# pic.net
KiCad netlist of a schematic drawn in Altium Designer
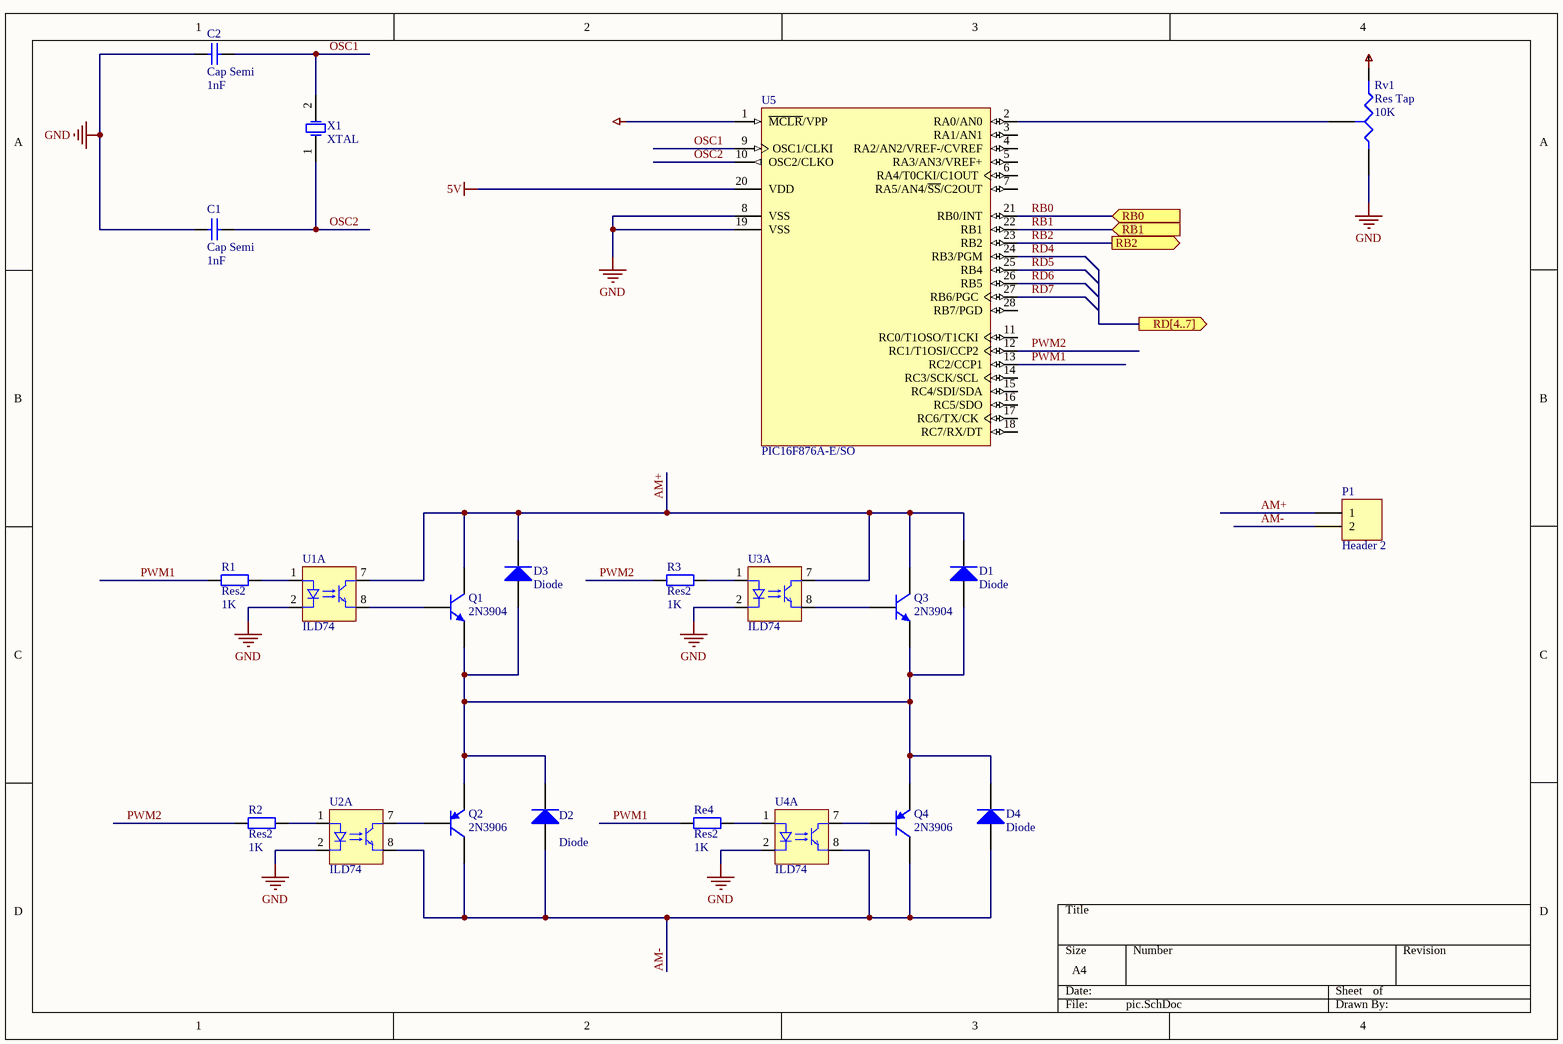
[diagram p0: pic.SchDoc]

(export (version "E")
  (design (tool "Eeschema 10.0.6"))
  (components
    (comp (ref "C1")
      (value "Cap Semi")
      (footprint "C1206")
      (description "Capacitor (Semiconductor SIM Model)")
      (fields (field (name "ALTIUM_VALUE") "1nF") (field (name "PUBLISHER") "Altium Limited"))
      (libsource (lib "Miscellaneous Devices") (part "Cap Semi"))
    )
    (comp (ref "C2")
      (value "Cap Semi")
      (footprint "C1206")
      (description "Capacitor (Semiconductor SIM Model)")
      (fields (field (name "ALTIUM_VALUE") "1nF") (field (name "PUBLISHER") "Altium Limited"))
      (libsource (lib "Miscellaneous Devices") (part "Cap Semi"))
    )
    (comp (ref "D1")
      (value "Diode")
      (footprint "SMC")
      (description "Default Diode")
      (fields (field (name "PUBLISHER") "Altium Limited"))
      (libsource (lib "Miscellaneous Devices") (part "Diode"))
    )
    (comp (ref "D2")
      (value "Diode")
      (footprint "SMC")
      (description "Default Diode")
      (fields (field (name "PUBLISHER") "Altium Limited"))
      (libsource (lib "Miscellaneous Devices") (part "Diode"))
    )
    (comp (ref "D3")
      (value "Diode")
      (footprint "SMC")
      (description "Default Diode")
      (fields (field (name "PUBLISHER") "Altium Limited"))
      (libsource (lib "Miscellaneous Devices") (part "Diode"))
    )
    (comp (ref "D4")
      (value "Diode")
      (footprint "SMC")
      (description "Default Diode")
      (fields (field (name "PUBLISHER") "Altium Limited"))
      (libsource (lib "Miscellaneous Devices") (part "Diode"))
    )
    (comp (ref "P1")
      (value "Header 2")
      (footprint "HDR1X2")
      (description "Header, 2-Pin")
      (fields (field (name "PUBLISHER") "Altium Limited"))
      (libsource (lib "Miscellaneous Connectors") (part "Header 2"))
    )
    (comp (ref "Q1")
      (value "2N3904")
      (footprint "TO-92A")
      (description "NPN General Purpose Amplifier")
      (fields (field (name "PUBLISHER") "Altium Limited"))
      (libsource (lib "Miscellaneous Devices") (part "2N3904"))
    )
    (comp (ref "Q2")
      (value "2N3906")
      (footprint "TO-92A")
      (description "PNP General Purpose Amplifier")
      (fields (field (name "PUBLISHER") "Altium Limited"))
      (libsource (lib "Miscellaneous Devices") (part "2N3906"))
    )
    (comp (ref "Q3")
      (value "2N3904")
      (footprint "TO-92A")
      (description "NPN General Purpose Amplifier")
      (fields (field (name "PUBLISHER") "Altium Limited"))
      (libsource (lib "Miscellaneous Devices") (part "2N3904"))
    )
    (comp (ref "Q4")
      (value "2N3906")
      (footprint "TO-92A")
      (description "PNP General Purpose Amplifier")
      (fields (field (name "PUBLISHER") "Altium Limited"))
      (libsource (lib "Miscellaneous Devices") (part "2N3906"))
    )
    (comp (ref "R1")
      (value "Res2")
      (footprint "AXIAL-0.4")
      (description "Resistor")
      (fields (field (name "ALTIUM_VALUE") "1K") (field (name "PUBLISHER") "Altium Limited"))
      (libsource (lib "Miscellaneous Devices") (part "Res2"))
    )
    (comp (ref "R2")
      (value "Res2")
      (footprint "AXIAL-0.4")
      (description "Resistor")
      (fields (field (name "ALTIUM_VALUE") "1K") (field (name "PUBLISHER") "Altium Limited"))
      (libsource (lib "Miscellaneous Devices") (part "Res2"))
    )
    (comp (ref "R3")
      (value "Res2")
      (footprint "AXIAL-0.4")
      (description "Resistor")
      (fields (field (name "ALTIUM_VALUE") "1K") (field (name "PUBLISHER") "Altium Limited"))
      (libsource (lib "Miscellaneous Devices") (part "Res2"))
    )
    (comp (ref "Re4")
      (value "Res2")
      (footprint "AXIAL-0.4")
      (description "Resistor")
      (fields (field (name "ALTIUM_VALUE") "1K") (field (name "PUBLISHER") "Altium Limited"))
      (libsource (lib "Miscellaneous Devices") (part "Res2"))
    )
    (comp (ref "Rv1")
      (value "Res Tap")
      (footprint "VR3")
      (description "Tapped Resistor")
      (fields (field (name "ALTIUM_VALUE") "10K") (field (name "PUBLISHER") "Altium Limited"))
      (libsource (lib "Miscellaneous Devices") (part "Res Tap"))
    )
    (comp (ref "U1")
      (value "ILD74")
      (footprint "DIP8")
      (description "Optocoupler, Phototransistor Output, Dual Channel, TTL Compatible, Pb-free")
      (fields (field (name "PUBLISHER") "Altium Limited"))
      (libsource (lib "Vishay Optoelectronic Optocoupler") (part "ILD74"))
    )
    (comp (ref "U2")
      (value "ILD74")
      (footprint "DIP8")
      (description "Optocoupler, Phototransistor Output, Dual Channel, TTL Compatible, Pb-free")
      (fields (field (name "PUBLISHER") "Altium Limited"))
      (libsource (lib "Vishay Optoelectronic Optocoupler") (part "ILD74"))
    )
    (comp (ref "U3")
      (value "ILD74")
      (footprint "DIP8")
      (description "Optocoupler, Phototransistor Output, Dual Channel, TTL Compatible, Pb-free")
      (fields (field (name "PUBLISHER") "Altium Limited"))
      (libsource (lib "Vishay Optoelectronic Optocoupler") (part "ILD74"))
    )
    (comp (ref "U4")
      (value "ILD74")
      (footprint "DIP8")
      (description "Optocoupler, Phototransistor Output, Dual Channel, TTL Compatible, Pb-free")
      (fields (field (name "PUBLISHER") "Altium Limited"))
      (libsource (lib "Vishay Optoelectronic Optocoupler") (part "ILD74"))
    )
    (comp (ref "U5")
      (value "PIC16F876A-E/SO")
      (footprint "SOIC-SO28_N")
      (fields (field (name "PUBLISHER") "Altium Limited"))
      (libsource (lib "Microchip Microcontroller 8-Bit PIC16") (part "PIC16F876A-E/SO"))
    )
    (comp (ref "X1")
      (value "XTAL")
      (footprint "R38")
      (description "Crystal Oscillator")
      (fields (field (name "PUBLISHER") "Altium Limited"))
      (libsource (lib "Miscellaneous Devices") (part "XTAL"))
    )
  )
  (nets
    (net (code "1") (name "/AM+") (class "Default")
      (node (ref "D1") (pin "2") (pinfunction "K_2") (pintype "passive"))
      (node (ref "D3") (pin "2") (pinfunction "K_2") (pintype "passive"))
      (node (ref "P1") (pin "1") (pinfunction "1_1") (pintype "passive"))
      (node (ref "Q1") (pin "3") (pinfunction "C_3") (pintype "passive"))
      (node (ref "Q3") (pin "3") (pinfunction "C_3") (pintype "passive"))
      (node (ref "U1") (pin "7") (pinfunction "C_7") (pintype "passive"))
      (node (ref "U3") (pin "7") (pinfunction "C_7") (pintype "passive"))
    )
    (net (code "2") (name "/AM-") (class "Default")
      (node (ref "D2") (pin "1") (pinfunction "A_1") (pintype "passive"))
      (node (ref "D4") (pin "1") (pinfunction "A_1") (pintype "passive"))
      (node (ref "P1") (pin "2") (pinfunction "2_2") (pintype "passive"))
      (node (ref "Q2") (pin "3") (pinfunction "C_3") (pintype "passive"))
      (node (ref "Q4") (pin "3") (pinfunction "C_3") (pintype "passive"))
      (node (ref "U2") (pin "8") (pinfunction "E_8") (pintype "passive"))
      (node (ref "U4") (pin "8") (pinfunction "E_8") (pintype "passive"))
    )
    (net (code "3") (name "/OSC1") (class "Default")
      (node (ref "C2") (pin "2") (pinfunction "2_2") (pintype "passive"))
      (node (ref "U5") (pin "9") (pinfunction "OSC1/CLKI_9") (pintype "input"))
      (node (ref "X1") (pin "2") (pinfunction "OSC2_2") (pintype "passive"))
    )
    (net (code "4") (name "/OSC2") (class "Default")
      (node (ref "C1") (pin "2") (pinfunction "2_2") (pintype "passive"))
      (node (ref "U5") (pin "10") (pinfunction "OSC2/CLKO_10") (pintype "output"))
      (node (ref "X1") (pin "1") (pinfunction "OSC1_1") (pintype "passive"))
    )
    (net (code "5") (name "/PWM1") (class "Default")
      (node (ref "R1") (pin "1") (pinfunction "1_1") (pintype "passive"))
      (node (ref "Re4") (pin "1") (pinfunction "1_1") (pintype "passive"))
      (node (ref "U5") (pin "13") (pinfunction "RC2/CCP1_13") (pintype "bidirectional"))
    )
    (net (code "6") (name "/PWM2") (class "Default")
      (node (ref "R2") (pin "1") (pinfunction "1_1") (pintype "passive"))
      (node (ref "R3") (pin "1") (pinfunction "1_1") (pintype "passive"))
      (node (ref "U5") (pin "12") (pinfunction "RC1/T1OSI/CCP2_12") (pintype "bidirectional"))
    )
    (net (code "7") (name "/RB0") (class "Default")
      (node (ref "U5") (pin "21") (pinfunction "RB0/INT_21") (pintype "bidirectional"))
    )
    (net (code "8") (name "/RB1") (class "Default")
      (node (ref "U5") (pin "22") (pinfunction "RB1_22") (pintype "bidirectional"))
    )
    (net (code "9") (name "/RB2") (class "Default")
      (node (ref "U5") (pin "23") (pinfunction "RB2_23") (pintype "bidirectional"))
    )
    (net (code "10") (name "/RD4") (class "Default")
      (node (ref "U5") (pin "24") (pinfunction "RB3/PGM_24") (pintype "bidirectional"))
    )
    (net (code "11") (name "/RD5") (class "Default")
      (node (ref "U5") (pin "25") (pinfunction "RB4_25") (pintype "bidirectional"))
    )
    (net (code "12") (name "/RD6") (class "Default")
      (node (ref "U5") (pin "26") (pinfunction "RB5_26") (pintype "bidirectional"))
    )
    (net (code "13") (name "/RD7") (class "Default")
      (node (ref "U5") (pin "27") (pinfunction "RB6/PGC_27") (pintype "bidirectional"))
    )
    (net (code "15") (name "5V") (class "Default")
      (node (ref "U5") (pin "20") (pinfunction "VDD_20") (pintype "power_in"))
    )
    (net (code "16") (name "<NO NET>") (class "Default")
      (node (ref "U5") (pin "1") (pinfunction "~{MCLR}/VPP_1") (pintype "input"))
    )
    (net (code "17") (name "GND") (class "Default")
      (node (ref "C1") (pin "1") (pinfunction "1_1") (pintype "passive"))
      (node (ref "C2") (pin "1") (pinfunction "1_1") (pintype "passive"))
      (node (ref "Rv1") (pin "1") (pinfunction "A_1") (pintype "passive"))
      (node (ref "U1") (pin "2") (pinfunction "K_2") (pintype "passive"))
      (node (ref "U2") (pin "2") (pinfunction "K_2") (pintype "passive"))
      (node (ref "U3") (pin "2") (pinfunction "K_2") (pintype "passive"))
      (node (ref "U4") (pin "2") (pinfunction "K_2") (pintype "passive"))
      (node (ref "U5") (pin "19") (pinfunction "VSS_19") (pintype "power_in"))
      (node (ref "U5") (pin "8") (pinfunction "VSS_8") (pintype "power_in"))
    )
    (net (code "18") (name "Net-(D1-A)") (class "Default")
      (node (ref "D1") (pin "1") (pinfunction "A_1") (pintype "passive"))
      (node (ref "D2") (pin "2") (pinfunction "K_2") (pintype "passive"))
      (node (ref "D3") (pin "1") (pinfunction "A_1") (pintype "passive"))
      (node (ref "D4") (pin "2") (pinfunction "K_2") (pintype "passive"))
      (node (ref "Q1") (pin "1") (pinfunction "E_1") (pintype "passive"))
      (node (ref "Q2") (pin "1") (pinfunction "E_1") (pintype "passive"))
      (node (ref "Q3") (pin "1") (pinfunction "E_1") (pintype "passive"))
      (node (ref "Q4") (pin "1") (pinfunction "E_1") (pintype "passive"))
    )
    (net (code "19") (name "Net-(Q1-B)") (class "Default")
      (node (ref "Q1") (pin "2") (pinfunction "B_2") (pintype "passive"))
      (node (ref "U1") (pin "8") (pinfunction "E_8") (pintype "passive"))
    )
    (net (code "20") (name "Net-(Q2-B)") (class "Default")
      (node (ref "Q2") (pin "2") (pinfunction "B_2") (pintype "passive"))
      (node (ref "U2") (pin "7") (pinfunction "C_7") (pintype "passive"))
    )
    (net (code "21") (name "Net-(Q3-B)") (class "Default")
      (node (ref "Q3") (pin "2") (pinfunction "B_2") (pintype "passive"))
      (node (ref "U3") (pin "8") (pinfunction "E_8") (pintype "passive"))
    )
    (net (code "22") (name "Net-(Q4-B)") (class "Default")
      (node (ref "Q4") (pin "2") (pinfunction "B_2") (pintype "passive"))
      (node (ref "U4") (pin "7") (pinfunction "C_7") (pintype "passive"))
    )
    (net (code "23") (name "Net-(Rv1-TAP)") (class "Default")
      (node (ref "Rv1") (pin "3") (pinfunction "TAP_3") (pintype "passive"))
      (node (ref "U5") (pin "2") (pinfunction "RA0/AN0_2") (pintype "bidirectional"))
    )
    (net (code "24") (name "Net-(U1A-A)") (class "Default")
      (node (ref "R1") (pin "2") (pinfunction "2_2") (pintype "passive"))
      (node (ref "U1") (pin "1") (pinfunction "A_1") (pintype "passive"))
    )
    (net (code "25") (name "Net-(U2A-A)") (class "Default")
      (node (ref "R2") (pin "2") (pinfunction "2_2") (pintype "passive"))
      (node (ref "U2") (pin "1") (pinfunction "A_1") (pintype "passive"))
    )
    (net (code "26") (name "Net-(U3A-A)") (class "Default")
      (node (ref "R3") (pin "2") (pinfunction "2_2") (pintype "passive"))
      (node (ref "U3") (pin "1") (pinfunction "A_1") (pintype "passive"))
    )
    (net (code "27") (name "Net-(U4A-A)") (class "Default")
      (node (ref "Re4") (pin "2") (pinfunction "2_2") (pintype "passive"))
      (node (ref "U4") (pin "1") (pinfunction "A_1") (pintype "passive"))
    )
    (net (code "28") (name "unconnected-(Rv1-B-Pad2)") (class "Default")
      (node (ref "Rv1") (pin "2") (pinfunction "B_2") (pintype "passive"))
    )
    (net (code "29") (name "unconnected-(U5-RA1{slash}AN1-Pad3)") (class "Default")
      (node (ref "U5") (pin "3") (pinfunction "RA1/AN1_3") (pintype "bidirectional"))
    )
    (net (code "30") (name "unconnected-(U5-RA2{slash}AN2{slash}VREF-{slash}CVREF-Pad4)") (class "Default")
      (node (ref "U5") (pin "4") (pinfunction "RA2/AN2/VREF-/CVREF_4") (pintype "bidirectional"))
    )
    (net (code "31") (name "unconnected-(U5-RA3{slash}AN3{slash}VREF+-Pad5)") (class "Default")
      (node (ref "U5") (pin "5") (pinfunction "RA3/AN3/VREF+_5") (pintype "bidirectional"))
    )
    (net (code "32") (name "unconnected-(U5-RA4{slash}T0CKI{slash}C1OUT-Pad6)") (class "Default")
      (node (ref "U5") (pin "6") (pinfunction "RA4/T0CKI/C1OUT_6") (pintype "bidirectional"))
    )
    (net (code "33") (name "unconnected-(U5-RA5{slash}AN4{slash}~{SS}{slash}C2OUT-Pad7)") (class "Default")
      (node (ref "U5") (pin "7") (pinfunction "RA5/AN4/~{SS}/C2OUT_7") (pintype "bidirectional"))
    )
    (net (code "34") (name "unconnected-(U5-RB7{slash}PGD-Pad28)") (class "Default")
      (node (ref "U5") (pin "28") (pinfunction "RB7/PGD_28") (pintype "bidirectional"))
    )
    (net (code "35") (name "unconnected-(U5-RC0{slash}T1OSO{slash}T1CKI-Pad11)") (class "Default")
      (node (ref "U5") (pin "11") (pinfunction "RC0/T1OSO/T1CKI_11") (pintype "bidirectional"))
    )
    (net (code "36") (name "unconnected-(U5-RC3{slash}SCK{slash}SCL-Pad14)") (class "Default")
      (node (ref "U5") (pin "14") (pinfunction "RC3/SCK/SCL_14") (pintype "bidirectional"))
    )
    (net (code "37") (name "unconnected-(U5-RC4{slash}SDI{slash}SDA-Pad15)") (class "Default")
      (node (ref "U5") (pin "15") (pinfunction "RC4/SDI/SDA_15") (pintype "bidirectional"))
    )
    (net (code "38") (name "unconnected-(U5-RC5{slash}SDO-Pad16)") (class "Default")
      (node (ref "U5") (pin "16") (pinfunction "RC5/SDO_16") (pintype "bidirectional"))
    )
    (net (code "39") (name "unconnected-(U5-RC6{slash}TX{slash}CK-Pad17)") (class "Default")
      (node (ref "U5") (pin "17") (pinfunction "RC6/TX/CK_17") (pintype "bidirectional"))
    )
    (net (code "40") (name "unconnected-(U5-RC7{slash}RX{slash}DT-Pad18)") (class "Default")
      (node (ref "U5") (pin "18") (pinfunction "RC7/RX/DT_18") (pintype "bidirectional"))
    )
  )
)
